# ADCCircuit.net
KiCad netlist of a schematic drawn in Altium Designer
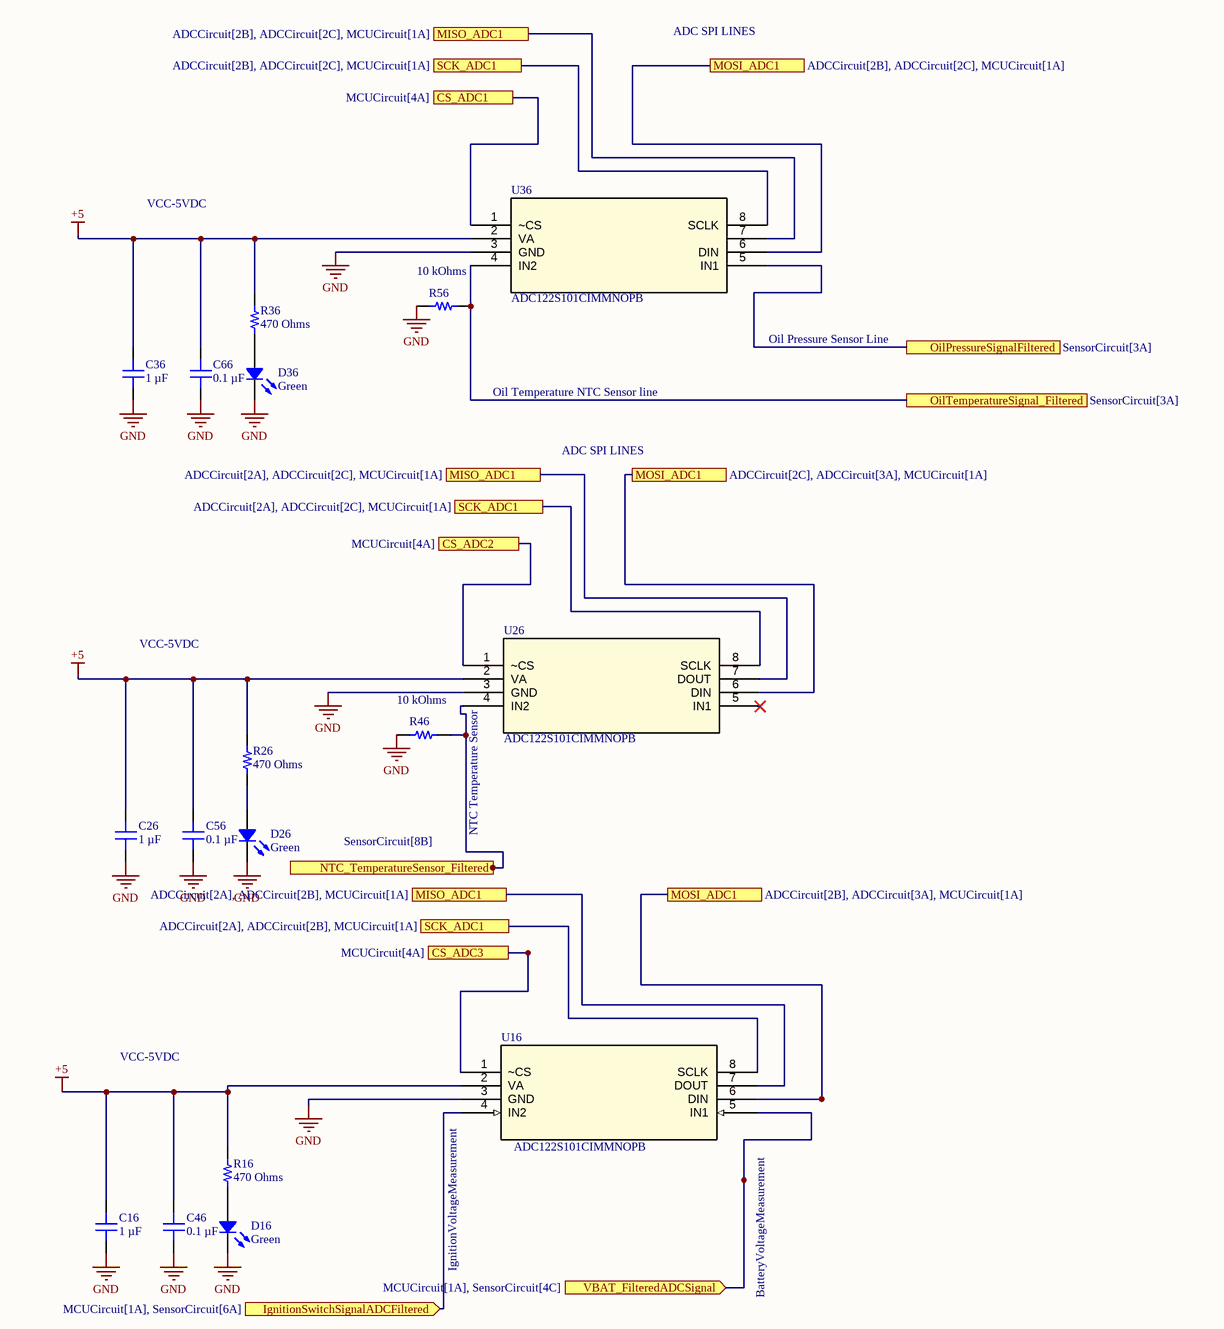
[diagram p0: ADCCircuit.SchDoc]

(export (version "E")
  (design (tool "Eeschema 10.0.6"))
  (components
    (comp (ref "C16")
      (value "1 µF")
      (footprint "C0805")
      (description "CAP CER 1UF 16V X7R 0805")
      (fields (field (name "PART NUMBER") "EMK212B7105KGHTR") (field (name "MANUFACTURER") "Taiyo Yuden"))
      (libsource (lib "Celestial Altium Library - altium_library") (part "Capacitor"))
    )
    (comp (ref "C26")
      (value "1 µF")
      (footprint "C0805")
      (description "CAP CER 1UF 16V X7R 0805")
      (fields (field (name "PART NUMBER") "EMK212B7105KGHTR") (field (name "MANUFACTURER") "Taiyo Yuden"))
      (libsource (lib "Celestial Altium Library - altium_library") (part "Capacitor"))
    )
    (comp (ref "C36")
      (value "1 µF")
      (footprint "C0805")
      (description "CAP CER 1UF 16V X7R 0805")
      (fields (field (name "PART NUMBER") "EMK212B7105KGHTR") (field (name "MANUFACTURER") "Taiyo Yuden"))
      (libsource (lib "Celestial Altium Library - altium_library") (part "Capacitor"))
    )
    (comp (ref "C46")
      (value "0.1 µF")
      (footprint "C0805")
      (description "CAP CER 0.1UF 16V X7R 0805")
      (fields
        (field (name "PART NUMBER") "0805B104K160CT")
        (field (name "MANUFACTURER") "Walsin Technology Corporation")
      )
      (libsource (lib "Celestial Altium Library - altium_library") (part "Capacitor"))
    )
    (comp (ref "C56")
      (value "0.1 µF")
      (footprint "C0805")
      (description "CAP CER 0.1UF 16V X7R 0805")
      (fields
        (field (name "PART NUMBER") "0805B104K160CT")
        (field (name "MANUFACTURER") "Walsin Technology Corporation")
      )
      (libsource (lib "Celestial Altium Library - altium_library") (part "Capacitor"))
    )
    (comp (ref "C66")
      (value "0.1 µF")
      (footprint "C0805")
      (description "CAP CER 0.1UF 16V X7R 0805")
      (fields
        (field (name "PART NUMBER") "0805B104K160CT")
        (field (name "MANUFACTURER") "Walsin Technology Corporation")
      )
      (libsource (lib "Celestial Altium Library - altium_library") (part "Capacitor"))
    )
    (comp (ref "D16")
      (value "Green")
      (footprint "LED 0805_2012 GREEN")
      (description "LED GREEN CLEAR 0805 SMD")
      (fields (field (name "PART NUMBER") "SM0805UGC") (field (name "MANUFACTURER") "Bivar Inc."))
      (libsource (lib "Celestial Altium Library - altium_library") (part "LED"))
    )
    (comp (ref "D26")
      (value "Green")
      (footprint "LED 0805_2012 GREEN")
      (description "LED GREEN CLEAR 0805 SMD")
      (fields (field (name "PART NUMBER") "SM0805UGC") (field (name "MANUFACTURER") "Bivar Inc."))
      (libsource (lib "Celestial Altium Library - altium_library") (part "LED"))
    )
    (comp (ref "D36")
      (value "Green")
      (footprint "LED 0805_2012 GREEN")
      (description "LED GREEN CLEAR 0805 SMD")
      (fields (field (name "PART NUMBER") "SM0805UGC") (field (name "MANUFACTURER") "Bivar Inc."))
      (libsource (lib "Celestial Altium Library - altium_library") (part "LED"))
    )
    (comp (ref "R16")
      (value "470 Ohms")
      (footprint "RES 0805_2012")
      (description "RES SMD 470 OHM 5% 1/8W 0805")
      (fields (field (name "PART NUMBER") "AC0805JR-07470RL") (field (name "MANUFACTURER") "Yageo"))
      (libsource (lib "Celestial Altium Library - altium_library") (part "Resistor"))
    )
    (comp (ref "R26")
      (value "470 Ohms")
      (footprint "RES 0805_2012")
      (description "RES SMD 470 OHM 5% 1/8W 0805")
      (fields (field (name "PART NUMBER") "AC0805JR-07470RL") (field (name "MANUFACTURER") "Yageo"))
      (libsource (lib "Celestial Altium Library - altium_library") (part "Resistor"))
    )
    (comp (ref "R36")
      (value "470 Ohms")
      (footprint "RES 0805_2012")
      (description "RES SMD 470 OHM 5% 1/8W 0805")
      (fields (field (name "PART NUMBER") "AC0805JR-07470RL") (field (name "MANUFACTURER") "Yageo"))
      (libsource (lib "Celestial Altium Library - altium_library") (part "Resistor"))
    )
    (comp (ref "R46")
      (value "10 kOhms")
      (footprint "RES 0805_2012")
      (description "RES 10K OHM 0.1% 1/5W 0805")
      (fields
        (field (name "PART NUMBER") "9-2176375-1")
        (field (name "MANUFACTURER") "TE Connectivity Passive Product")
      )
      (libsource (lib "Celestial Altium Library - altium_library") (part "Resistor"))
    )
    (comp (ref "R56")
      (value "10 kOhms")
      (footprint "RES 0805_2012")
      (description "RES 10K OHM 0.1% 1/5W 0805")
      (fields
        (field (name "PART NUMBER") "9-2176375-1")
        (field (name "MANUFACTURER") "TE Connectivity Passive Product")
      )
      (libsource (lib "Celestial Altium Library - altium_library") (part "Resistor"))
    )
    (comp (ref "U16")
      (value "ADC122S101CIMMNOPB")
      (footprint "MUA08A")
      (description "No Description Available")
      (libsource (lib "ADC122S101CIMMNOPB") (part "ADC122S101CIMMNOPB"))
    )
    (comp (ref "U26")
      (value "ADC122S101CIMMNOPB")
      (footprint "MUA08A")
      (description "No Description Available")
      (libsource (lib "ADC122S101CIMMNOPB") (part "ADC122S101CIMMNOPB"))
    )
    (comp (ref "U36")
      (value "ADC122S101CIMMNOPB")
      (footprint "MUA08A")
      (description "No Description Available")
      (libsource (lib "ADC122S101CIMMNOPB") (part "ADC122S101CIMMNOPB"))
    )
  )
  (nets
    (net (code "1") (name "+5") (class "Default")
      (node (ref "C16") (pin "2") (pinfunction "2_2") (pintype "passive"))
      (node (ref "C26") (pin "2") (pinfunction "2_2") (pintype "passive"))
      (node (ref "C36") (pin "2") (pinfunction "2_2") (pintype "passive"))
      (node (ref "C46") (pin "2") (pinfunction "2_2") (pintype "passive"))
      (node (ref "C56") (pin "2") (pinfunction "2_2") (pintype "passive"))
      (node (ref "C66") (pin "2") (pinfunction "2_2") (pintype "passive"))
      (node (ref "R16") (pin "2") (pinfunction "2_2") (pintype "passive"))
      (node (ref "R26") (pin "2") (pinfunction "2_2") (pintype "passive"))
      (node (ref "R36") (pin "2") (pinfunction "2_2") (pintype "passive"))
      (node (ref "U16") (pin "2") (pinfunction "VA_2") (pintype "passive"))
      (node (ref "U26") (pin "2") (pinfunction "VA_2") (pintype "passive"))
      (node (ref "U36") (pin "2") (pinfunction "VA_2") (pintype "passive"))
    )
    (net (code "2") (name "/CS_ADC1") (class "Default")
      (node (ref "U36") (pin "1") (pinfunction "~CS_1") (pintype "passive"))
    )
    (net (code "3") (name "/CS_ADC2") (class "Default")
      (node (ref "U26") (pin "1") (pinfunction "~CS_1") (pintype "passive"))
    )
    (net (code "4") (name "/CS_ADC3") (class "Default")
      (node (ref "U16") (pin "1") (pinfunction "~CS_1") (pintype "passive"))
    )
    (net (code "5") (name "/IgnitionSwitchSignalADCFiltered") (class "Default")
      (node (ref "U16") (pin "4") (pinfunction "IN2_4") (pintype "passive"))
    )
    (net (code "6") (name "/MISO_ADC1") (class "Default")
      (node (ref "U16") (pin "7") (pinfunction "DOUT_7") (pintype "passive"))
      (node (ref "U26") (pin "7") (pinfunction "DOUT_7") (pintype "passive"))
      (node (ref "U36") (pin "7") (pinfunction "DOUT_7") (pintype "passive"))
    )
    (net (code "7") (name "/MOSI_ADC1") (class "Default")
      (node (ref "U16") (pin "6") (pinfunction "DIN_6") (pintype "passive"))
      (node (ref "U26") (pin "6") (pinfunction "DIN_6") (pintype "passive"))
      (node (ref "U36") (pin "6") (pinfunction "DIN_6") (pintype "passive"))
    )
    (net (code "8") (name "/NTC_TemperatureSensor_Filtered") (class "Default")
      (node (ref "R46") (pin "2") (pinfunction "2_2") (pintype "passive"))
      (node (ref "U26") (pin "4") (pinfunction "IN2_4") (pintype "passive"))
    )
    (net (code "9") (name "/OilPressureSignalFiltered") (class "Default")
      (node (ref "U36") (pin "5") (pinfunction "IN1_5") (pintype "passive"))
    )
    (net (code "10") (name "/OilTemperatureSignal_Filtered") (class "Default")
      (node (ref "R56") (pin "2") (pinfunction "2_2") (pintype "passive"))
      (node (ref "U36") (pin "4") (pinfunction "IN2_4") (pintype "passive"))
    )
    (net (code "11") (name "/SCK_ADC1") (class "Default")
      (node (ref "U16") (pin "8") (pinfunction "SCLK_8") (pintype "passive"))
      (node (ref "U26") (pin "8") (pinfunction "SCLK_8") (pintype "passive"))
      (node (ref "U36") (pin "8") (pinfunction "SCLK_8") (pintype "passive"))
    )
    (net (code "12") (name "/VBAT_FilteredADCSignal") (class "Default")
      (node (ref "U16") (pin "5") (pinfunction "IN1_5") (pintype "passive"))
    )
    (net (code "13") (name "GND") (class "Default")
      (node (ref "C16") (pin "1") (pinfunction "1_1") (pintype "passive"))
      (node (ref "C26") (pin "1") (pinfunction "1_1") (pintype "passive"))
      (node (ref "C36") (pin "1") (pinfunction "1_1") (pintype "passive"))
      (node (ref "C46") (pin "1") (pinfunction "1_1") (pintype "passive"))
      (node (ref "C56") (pin "1") (pinfunction "1_1") (pintype "passive"))
      (node (ref "C66") (pin "1") (pinfunction "1_1") (pintype "passive"))
      (node (ref "D16") (pin "2") (pinfunction "2_2") (pintype "passive"))
      (node (ref "D26") (pin "2") (pinfunction "2_2") (pintype "passive"))
      (node (ref "D36") (pin "2") (pinfunction "2_2") (pintype "passive"))
      (node (ref "R46") (pin "1") (pinfunction "1_1") (pintype "passive"))
      (node (ref "R56") (pin "1") (pinfunction "1_1") (pintype "passive"))
      (node (ref "U16") (pin "3") (pinfunction "GND_3") (pintype "passive"))
      (node (ref "U26") (pin "3") (pinfunction "GND_3") (pintype "passive"))
      (node (ref "U36") (pin "3") (pinfunction "GND_3") (pintype "passive"))
    )
    (net (code "14") (name "Net-(D16-Pad1)") (class "Default")
      (node (ref "D16") (pin "1") (pinfunction "1_1") (pintype "passive"))
      (node (ref "R16") (pin "1") (pinfunction "1_1") (pintype "passive"))
    )
    (net (code "15") (name "Net-(D26-Pad1)") (class "Default")
      (node (ref "D26") (pin "1") (pinfunction "1_1") (pintype "passive"))
      (node (ref "R26") (pin "1") (pinfunction "1_1") (pintype "passive"))
    )
    (net (code "16") (name "Net-(D36-Pad1)") (class "Default")
      (node (ref "D36") (pin "1") (pinfunction "1_1") (pintype "passive"))
      (node (ref "R36") (pin "1") (pinfunction "1_1") (pintype "passive"))
    )
    (net (code "17") (name "unconnected-(U26-IN1-Pad5)") (class "Default")
      (node (ref "U26") (pin "5") (pinfunction "IN1_5") (pintype "passive+no_connect"))
    )
  )
)
